# 7_-CONNECTORS.net
KiCad netlist of a schematic drawn in Altium Designer
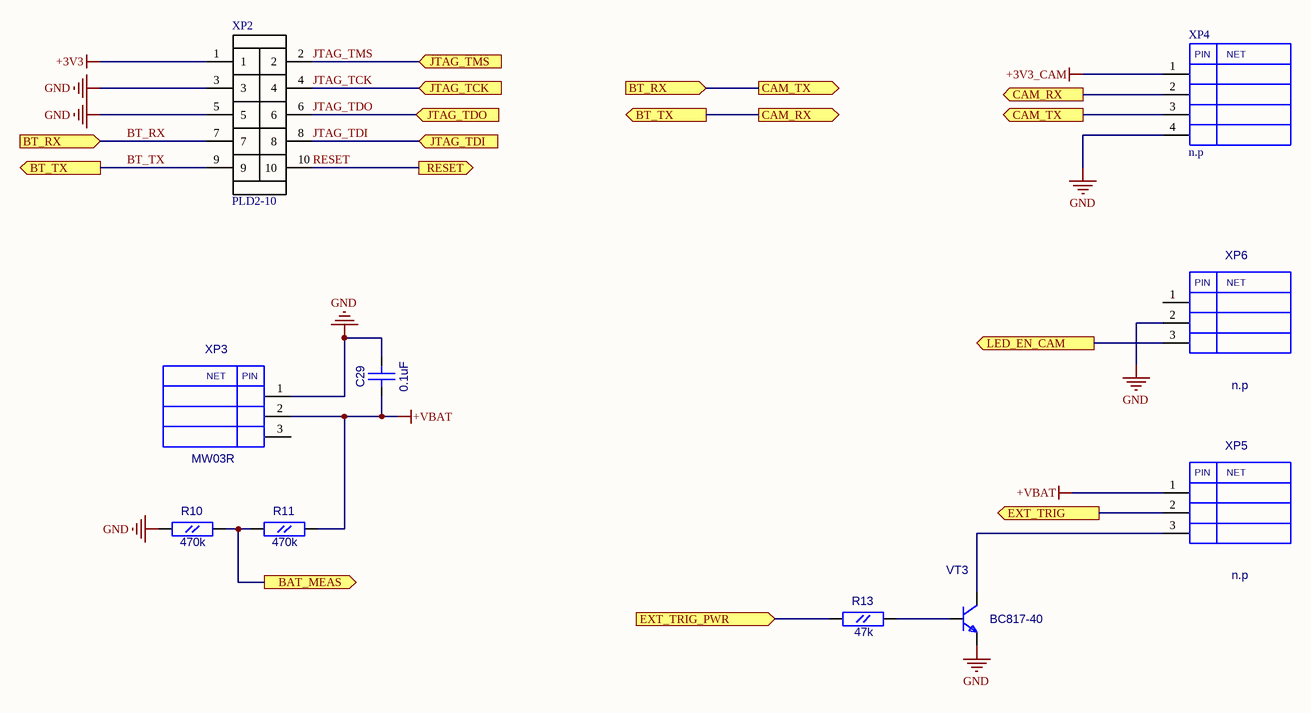
[diagram p0: [7]-CONNECTORS.SchDoc]

(export (version "E")
  (design (tool "Eeschema 10.0.6"))
  (components
    (comp (ref "C29")
      (value "0.1uF")
      (footprint "CC0603")
      (description "CC0603")
      (libsource (lib "fizik_lib") (part "CC0603"))
    )
    (comp (ref "R10")
      (value "470k")
      (footprint "RC0603")
      (description "RC0603")
      (libsource (lib "fizik_lib") (part "RC0603"))
    )
    (comp (ref "R11")
      (value "470k")
      (footprint "RC0603")
      (description "RC0603")
      (libsource (lib "fizik_lib") (part "RC0603"))
    )
    (comp (ref "R13")
      (value "47k")
      (footprint "RC0603")
      (description "RC0603")
      (libsource (lib "fizik_lib") (part "RC0603"))
    )
    (comp (ref "VT3")
      (value "BC817-40")
      (footprint "SOT-23(123)")
      (description "NPN 500ma transistor")
      (libsource (lib "fizik_lib") (part "BC846BLT1"))
    )
    (comp (ref "XP2")
      (value "PLD2-10")
      (footprint "PLD2-10")
      (libsource (lib "gprs_modem_2") (part "PLD2-10"))
    )
    (comp (ref "XP3") (value "MW03R") (footprint "MW03R") (libsource (lib "fizik_lib") (part "MW03R")))
    (comp (ref "XP4")
      (value "n.p")
      (footprint "PLS2-04")
      (description "PLS2-04")
      (libsource (lib "fizik_lib") (part "PLS2-04"))
    )
    (comp (ref "XP5")
      (value "n.p")
      (footprint "PLS-03")
      (description "PLS03")
      (libsource (lib "fizik_lib") (part "PLS03"))
    )
    (comp (ref "XP6")
      (value "n.p")
      (footprint "PLS2-03")
      (description "PLS2-03")
      (libsource (lib "fizik_lib") (part "PLS2-03"))
    )
  )
  (nets
    (net (code "1") (name "+3V3") (class "Default")
      (node (ref "XP2") (pin "1") (pinfunction "1_1") (pintype "passive"))
    )
    (net (code "2") (name "+3V3_CAM") (class "Default")
      (node (ref "XP4") (pin "1") (pinfunction "1_1") (pintype "passive"))
    )
    (net (code "3") (name "+VBAT") (class "Default")
      (node (ref "C29") (pin "1") (pinfunction "A_1") (pintype "passive"))
      (node (ref "R11") (pin "2") (pinfunction "B_2") (pintype "passive"))
      (node (ref "XP3") (pin "2") (pinfunction "2_2") (pintype "passive"))
      (node (ref "XP5") (pin "1") (pinfunction "1_1") (pintype "passive"))
    )
    (net (code "4") (name "/BAT_MEAS") (class "Default")
      (node (ref "R10") (pin "2") (pinfunction "B_2") (pintype "passive"))
      (node (ref "R11") (pin "1") (pinfunction "A_1") (pintype "passive"))
    )
    (net (code "5") (name "/BT_RX") (class "Default")
      (node (ref "XP2") (pin "7") (pinfunction "7_7") (pintype "passive"))
      (node (ref "XP4") (pin "3") (pinfunction "3_3") (pintype "passive"))
    )
    (net (code "6") (name "/BT_TX") (class "Default")
      (node (ref "XP2") (pin "9") (pinfunction "9_9") (pintype "passive"))
      (node (ref "XP4") (pin "2") (pinfunction "2_2") (pintype "passive"))
    )
    (net (code "7") (name "/EXT_TRIG") (class "Default")
      (node (ref "XP5") (pin "2") (pinfunction "2_2") (pintype "passive"))
    )
    (net (code "8") (name "/EXT_TRIG_PWR") (class "Default")
      (node (ref "R13") (pin "1") (pinfunction "A_1") (pintype "passive"))
    )
    (net (code "9") (name "/JTAG_TCK") (class "Default")
      (node (ref "XP2") (pin "4") (pinfunction "4_4") (pintype "passive"))
    )
    (net (code "10") (name "/JTAG_TDI") (class "Default")
      (node (ref "XP2") (pin "8") (pinfunction "8_8") (pintype "passive"))
    )
    (net (code "11") (name "/JTAG_TDO") (class "Default")
      (node (ref "XP2") (pin "6") (pinfunction "6_6") (pintype "passive"))
    )
    (net (code "12") (name "/JTAG_TMS") (class "Default")
      (node (ref "XP2") (pin "2") (pinfunction "2_2") (pintype "passive"))
    )
    (net (code "13") (name "/LED_EN_CAM") (class "Default")
      (node (ref "XP6") (pin "3") (pinfunction "3_3") (pintype "passive"))
    )
    (net (code "14") (name "/RESET") (class "Default")
      (node (ref "XP2") (pin "10") (pinfunction "10_10") (pintype "passive"))
    )
    (net (code "15") (name "GND") (class "Default")
      (node (ref "C29") (pin "2") (pinfunction "B_2") (pintype "passive"))
      (node (ref "R10") (pin "1") (pinfunction "A_1") (pintype "passive"))
      (node (ref "VT3") (pin "2") (pinfunction "E_2") (pintype "passive"))
      (node (ref "XP2") (pin "3") (pinfunction "3_3") (pintype "passive"))
      (node (ref "XP2") (pin "5") (pinfunction "5_5") (pintype "passive"))
      (node (ref "XP3") (pin "1") (pinfunction "1_1") (pintype "passive"))
      (node (ref "XP4") (pin "4") (pinfunction "4_4") (pintype "passive"))
      (node (ref "XP6") (pin "2") (pinfunction "2_2") (pintype "passive"))
    )
    (net (code "16") (name "Net-(R13-B)") (class "Default")
      (node (ref "R13") (pin "2") (pinfunction "B_2") (pintype "passive"))
      (node (ref "VT3") (pin "1") (pinfunction "B_1") (pintype "passive"))
    )
    (net (code "17") (name "Net-(VT3-C)") (class "Default")
      (node (ref "VT3") (pin "3") (pinfunction "C_3") (pintype "passive"))
      (node (ref "XP5") (pin "3") (pinfunction "3_3") (pintype "passive"))
    )
    (net (code "18") (name "unconnected-(XP3-Pad3)") (class "Default")
      (node (ref "XP3") (pin "3") (pinfunction "3_3") (pintype "passive"))
    )
    (net (code "19") (name "unconnected-(XP6-Pad1)") (class "Default")
      (node (ref "XP6") (pin "1") (pinfunction "1_1") (pintype "passive"))
    )
  )
)
